# STM32H730_PINOUT.net
KiCad netlist of a schematic drawn in Altium Designer
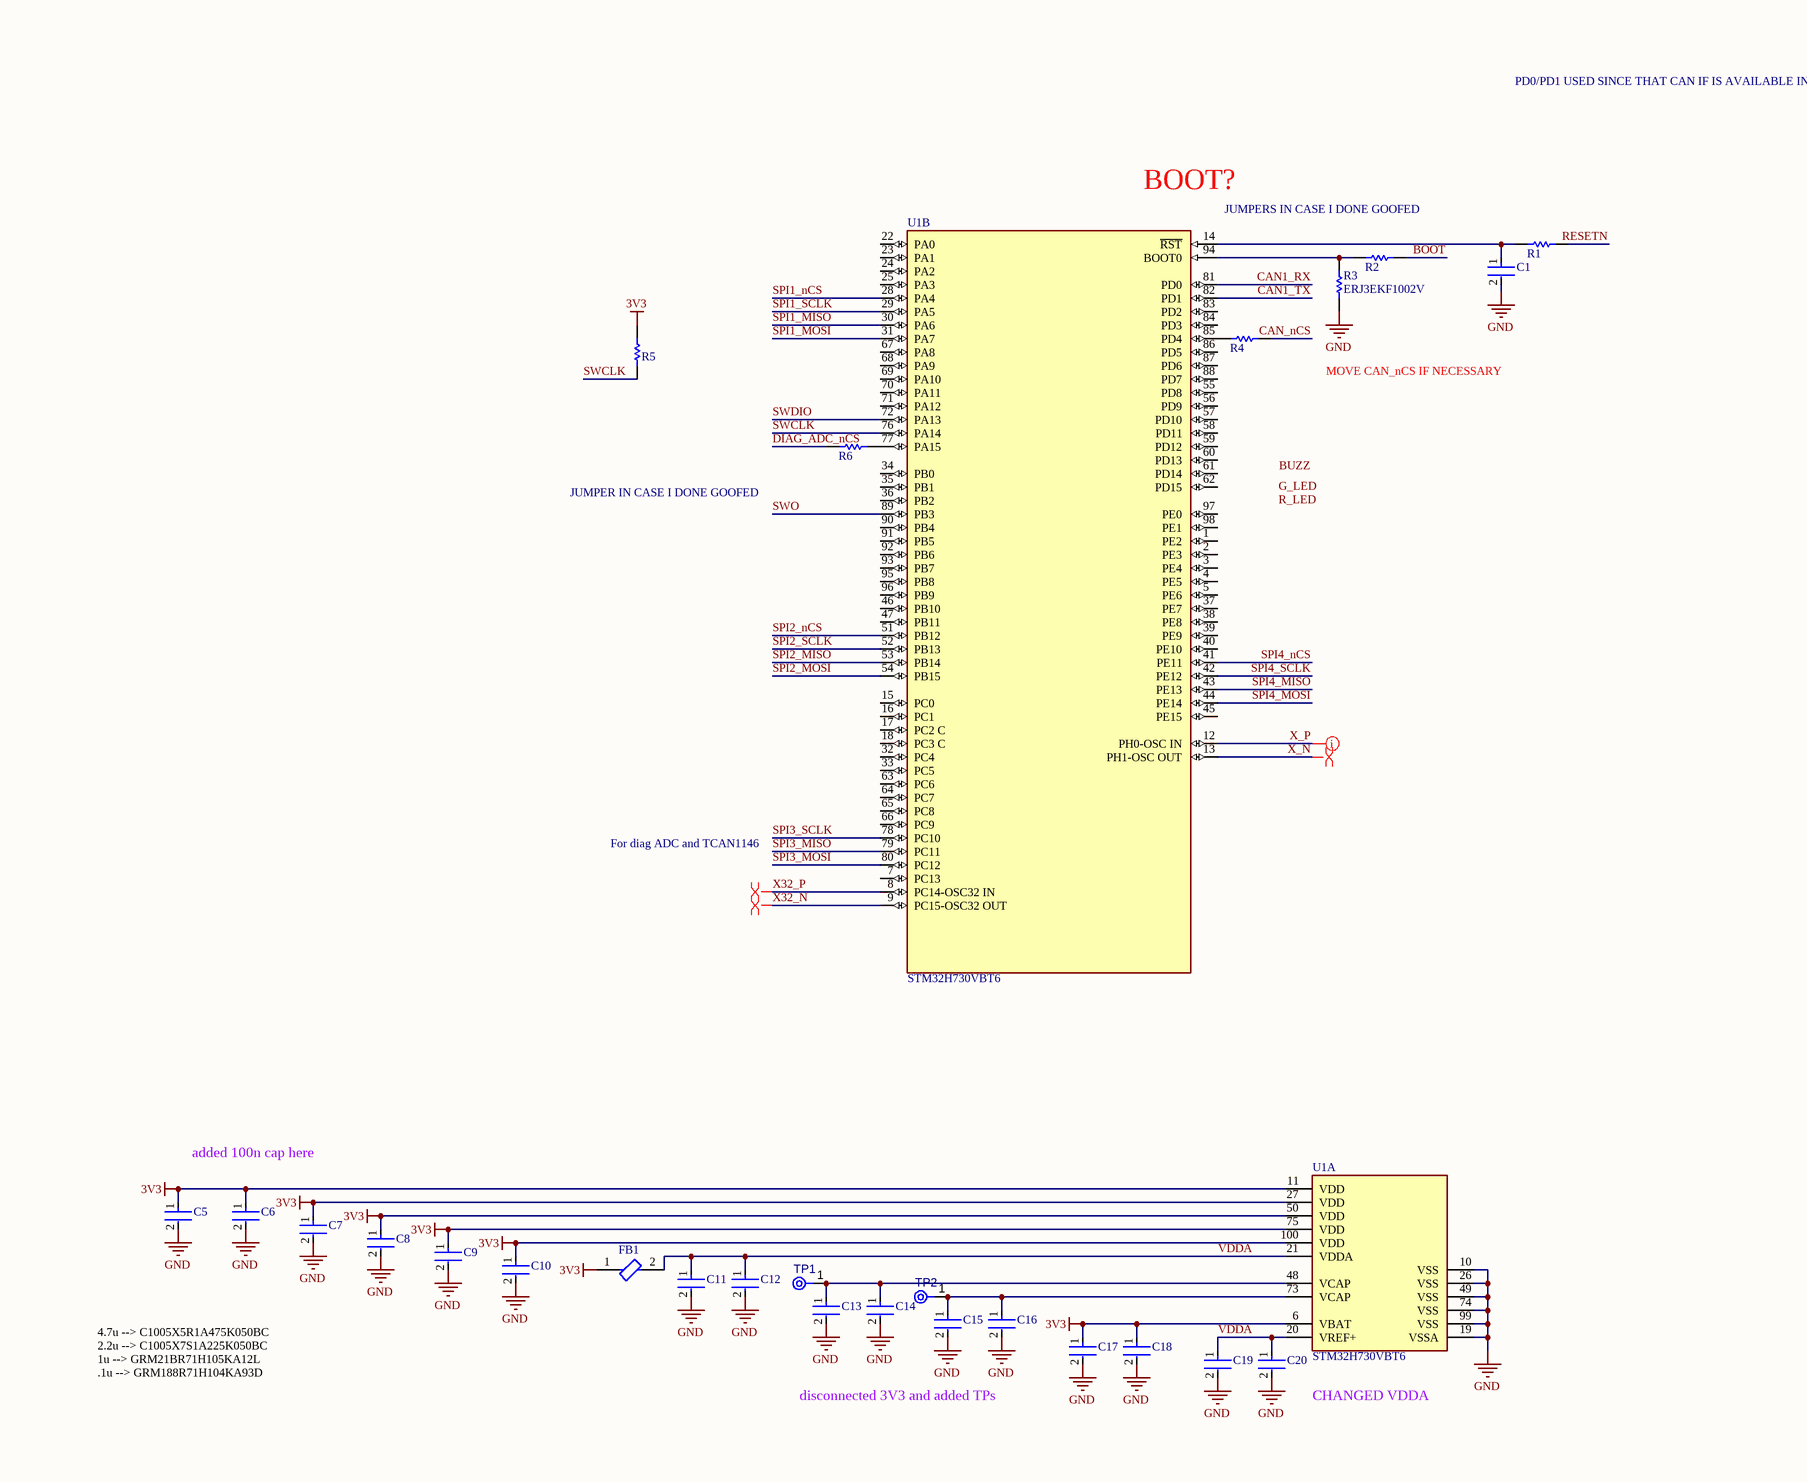
[diagram p0: STM32H730_PINOUT.SchDoc, top left]
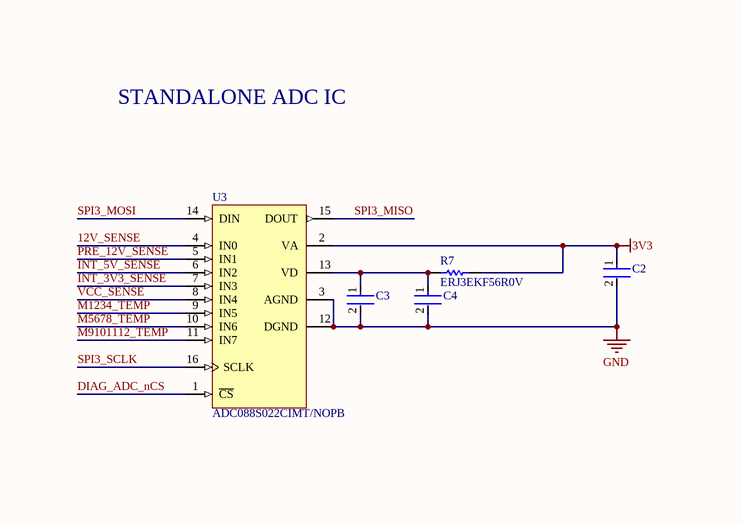
[diagram p1: STM32H730_PINOUT.SchDoc, top middle]
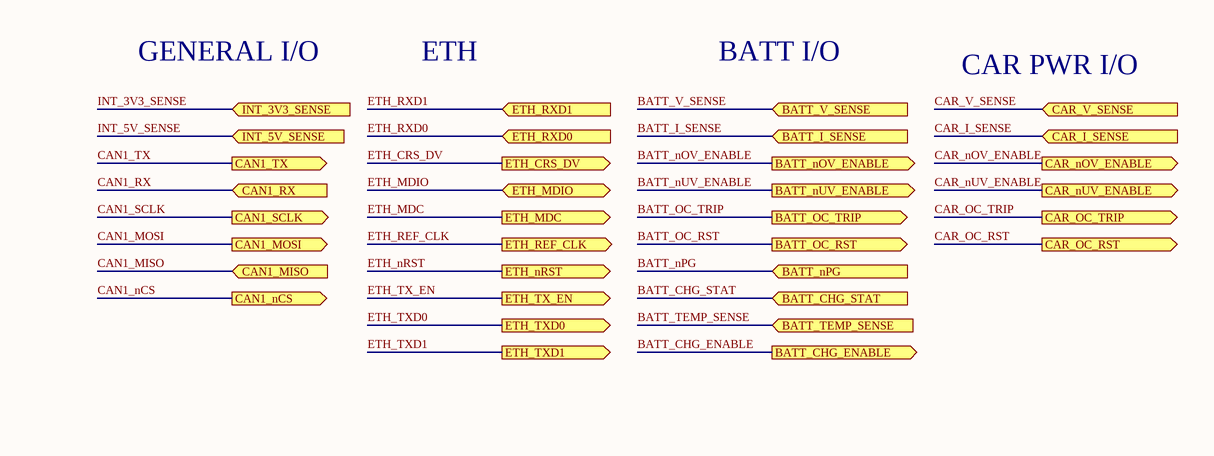
[diagram p2: STM32H730_PINOUT.SchDoc, top right]
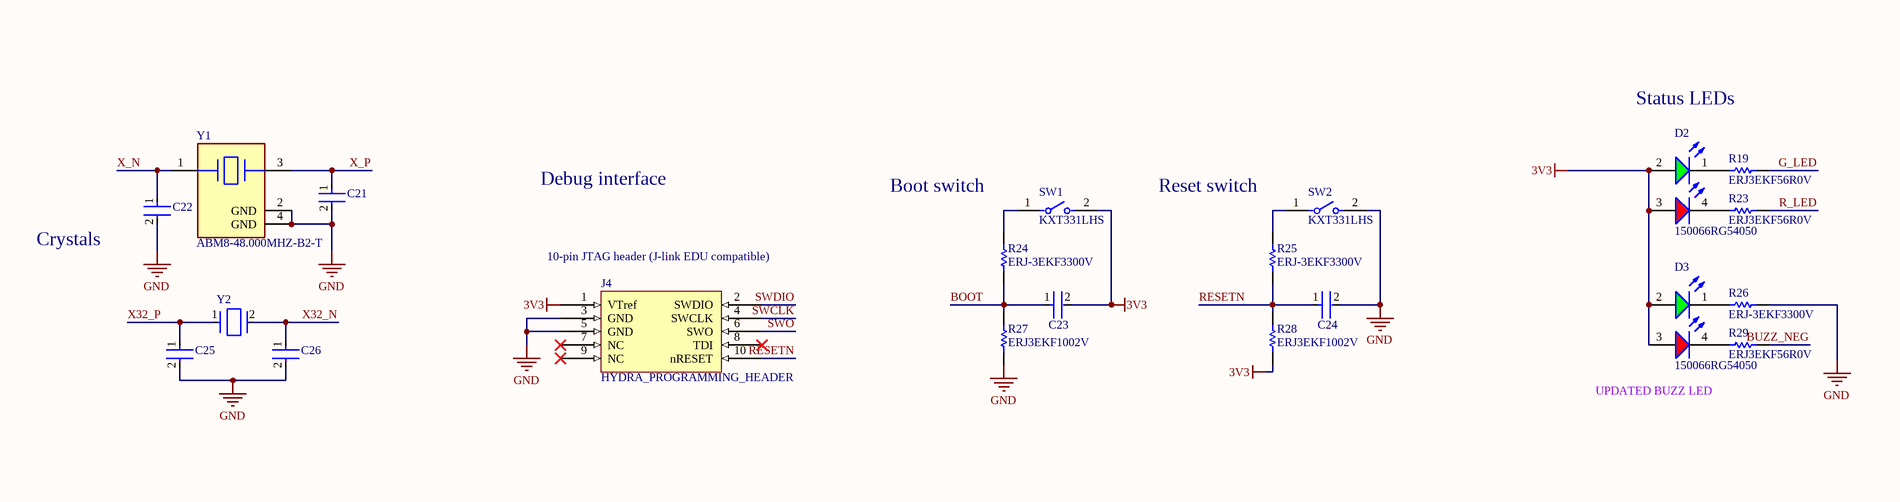
[diagram p3: STM32H730_PINOUT.SchDoc, bottom left]
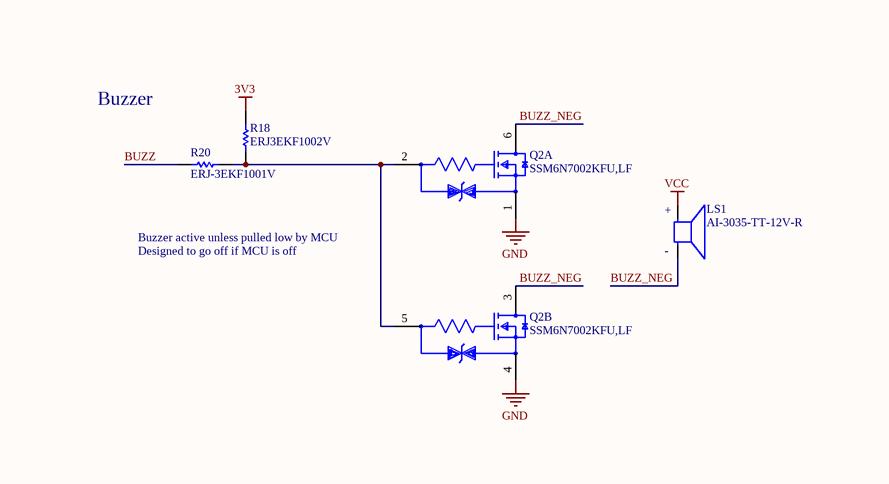
[diagram p4: STM32H730_PINOUT.SchDoc, bottom middle]
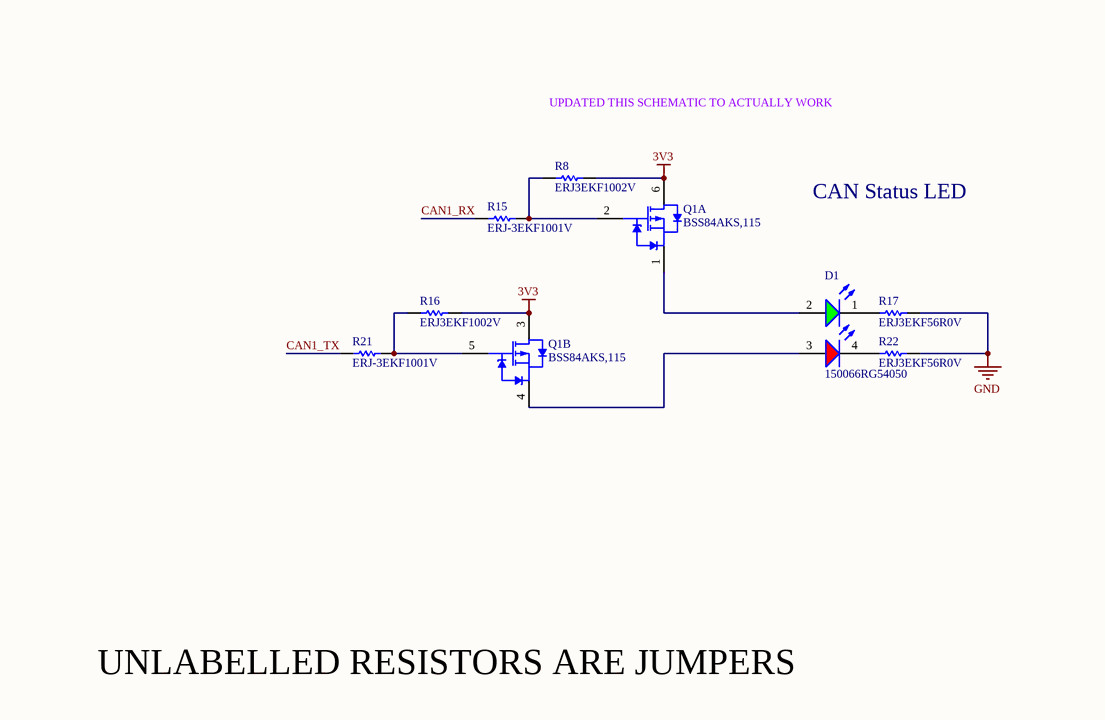
[diagram p5: STM32H730_PINOUT.SchDoc, bottom right]

(export (version "E")
  (design (tool "Eeschema 10.0.6"))
  (components
    (comp (ref "C1")
      (value "GRM188R71H104KA93D")
      (footprint "FP-0402-L_1_0_0_05-W_0_5-IPC_A")
      (description "LARGE PADS, 0402 CAP, CHANGE COMMENT TO MATCH REAL P/N")
      (libsource (lib "Space Concordia") (part "b4654b650e69147ec39a6b967a45e02"))
    )
    (comp (ref "C2")
      (value "GRM188R71H104KA93D")
      (footprint "FP-0402-L_1_0_0_05-W_0_5-IPC_A")
      (description "LARGE PADS, 0402 CAP, CHANGE COMMENT TO MATCH REAL P/N")
      (libsource (lib "Space Concordia") (part "b4654b650e69147ec39a6b967a45e02"))
    )
    (comp (ref "C3")
      (value "GRM188R71H104KA93D")
      (footprint "FP-0402-L_1_0_0_05-W_0_5-IPC_A")
      (description "LARGE PADS, 0402 CAP, CHANGE COMMENT TO MATCH REAL P/N")
      (libsource (lib "Space Concordia") (part "b4654b650e69147ec39a6b967a45e02"))
    )
    (comp (ref "C4")
      (value "GRM188R71H104KA93D")
      (footprint "FP-0402-L_1_0_0_05-W_0_5-IPC_A")
      (description "LARGE PADS, 0402 CAP, CHANGE COMMENT TO MATCH REAL P/N")
      (libsource (lib "Space Concordia") (part "b4654b650e69147ec39a6b967a45e02"))
    )
    (comp (ref "C5")
      (value "C1005X5R1A475K050BC")
      (footprint "FP-0402-L_1_0_0_05-W_0_5-IPC_A")
      (description "LARGE PADS, 0402 CAP, CHANGE COMMENT TO MATCH REAL P/N")
      (libsource (lib "Space Concordia") (part "b4654b650e69147ec39a6b967a45e02"))
    )
    (comp (ref "C6")
      (value "GRM188R71H104KA93D")
      (footprint "FP-0402-L_1_0_0_05-W_0_5-IPC_A")
      (description "LARGE PADS, 0402 CAP, CHANGE COMMENT TO MATCH REAL P/N")
      (libsource (lib "Space Concordia") (part "b4654b650e69147ec39a6b967a45e02"))
    )
    (comp (ref "C7")
      (value "GRM188R71H104KA93D")
      (footprint "FP-0402-L_1_0_0_05-W_0_5-IPC_A")
      (description "LARGE PADS, 0402 CAP, CHANGE COMMENT TO MATCH REAL P/N")
      (libsource (lib "Space Concordia") (part "b4654b650e69147ec39a6b967a45e02"))
    )
    (comp (ref "C8")
      (value "GRM188R71H104KA93D")
      (footprint "FP-0402-L_1_0_0_05-W_0_5-IPC_A")
      (description "LARGE PADS, 0402 CAP, CHANGE COMMENT TO MATCH REAL P/N")
      (libsource (lib "Space Concordia") (part "b4654b650e69147ec39a6b967a45e02"))
    )
    (comp (ref "C9")
      (value "GRM188R71H104KA93D")
      (footprint "FP-0402-L_1_0_0_05-W_0_5-IPC_A")
      (description "LARGE PADS, 0402 CAP, CHANGE COMMENT TO MATCH REAL P/N")
      (libsource (lib "Space Concordia") (part "b4654b650e69147ec39a6b967a45e02"))
    )
    (comp (ref "C10")
      (value "GRM188R71H104KA93D")
      (footprint "FP-0402-L_1_0_0_05-W_0_5-IPC_A")
      (description "LARGE PADS, 0402 CAP, CHANGE COMMENT TO MATCH REAL P/N")
      (libsource (lib "Space Concordia") (part "b4654b650e69147ec39a6b967a45e02"))
    )
    (comp (ref "C11")
      (value "GRM21BR71H105KA12L")
      (footprint "FP-0402-L_1_0_0_05-W_0_5-IPC_A")
      (description "LARGE PADS, 0402 CAP, CHANGE COMMENT TO MATCH REAL P/N")
      (libsource (lib "Space Concordia") (part "b4654b650e69147ec39a6b967a45e02"))
    )
    (comp (ref "C12")
      (value "GRM188R71H104KA93D")
      (footprint "FP-0402-L_1_0_0_05-W_0_5-IPC_A")
      (description "LARGE PADS, 0402 CAP, CHANGE COMMENT TO MATCH REAL P/N")
      (libsource (lib "Space Concordia") (part "b4654b650e69147ec39a6b967a45e02"))
    )
    (comp (ref "C13")
      (value "C1005X7S1A225K050BC")
      (footprint "FP-0402-L_1_0_0_05-W_0_5-IPC_A")
      (description "LARGE PADS, 0402 CAP, CHANGE COMMENT TO MATCH REAL P/N")
      (libsource (lib "Space Concordia") (part "b4654b650e69147ec39a6b967a45e02"))
    )
    (comp (ref "C14")
      (value "GRM188R71H104KA93D")
      (footprint "FP-0402-L_1_0_0_05-W_0_5-IPC_A")
      (description "LARGE PADS, 0402 CAP, CHANGE COMMENT TO MATCH REAL P/N")
      (libsource (lib "Space Concordia") (part "b4654b650e69147ec39a6b967a45e02"))
    )
    (comp (ref "C15")
      (value "C1005X7S1A225K050BC")
      (footprint "FP-0402-L_1_0_0_05-W_0_5-IPC_A")
      (description "LARGE PADS, 0402 CAP, CHANGE COMMENT TO MATCH REAL P/N")
      (libsource (lib "Space Concordia") (part "b4654b650e69147ec39a6b967a45e02"))
    )
    (comp (ref "C16")
      (value "GRM188R71H104KA93D")
      (footprint "FP-0402-L_1_0_0_05-W_0_5-IPC_A")
      (description "LARGE PADS, 0402 CAP, CHANGE COMMENT TO MATCH REAL P/N")
      (libsource (lib "Space Concordia") (part "b4654b650e69147ec39a6b967a45e02"))
    )
    (comp (ref "C17")
      (value "GRM21BR71H105KA12L")
      (footprint "FP-0402-L_1_0_0_05-W_0_5-IPC_A")
      (description "LARGE PADS, 0402 CAP, CHANGE COMMENT TO MATCH REAL P/N")
      (libsource (lib "Space Concordia") (part "b4654b650e69147ec39a6b967a45e02"))
    )
    (comp (ref "C18")
      (value "GRM188R71H104KA93D")
      (footprint "FP-0402-L_1_0_0_05-W_0_5-IPC_A")
      (description "LARGE PADS, 0402 CAP, CHANGE COMMENT TO MATCH REAL P/N")
      (libsource (lib "Space Concordia") (part "b4654b650e69147ec39a6b967a45e02"))
    )
    (comp (ref "C19")
      (value "GRM21BR71H105KA12L")
      (footprint "FP-0402-L_1_0_0_05-W_0_5-IPC_A")
      (description "LARGE PADS, 0402 CAP, CHANGE COMMENT TO MATCH REAL P/N")
      (libsource (lib "Space Concordia") (part "b4654b650e69147ec39a6b967a45e02"))
    )
    (comp (ref "C20")
      (value "GRM188R71H104KA93D")
      (footprint "FP-0402-L_1_0_0_05-W_0_5-IPC_A")
      (description "LARGE PADS, 0402 CAP, CHANGE COMMENT TO MATCH REAL P/N")
      (libsource (lib "Space Concordia") (part "b4654b650e69147ec39a6b967a45e02"))
    )
    (comp (ref "C21")
      (value "DNO")
      (footprint "FP-0402-L_1_0_0_05-W_0_5-IPC_A")
      (description "LARGE PADS, 0402 CAP, CHANGE COMMENT TO MATCH REAL P/N")
      (libsource (lib "Space Concordia") (part "b4654b650e69147ec39a6b967a45e02"))
    )
    (comp (ref "C22")
      (value "DNO")
      (footprint "FP-0402-L_1_0_0_05-W_0_5-IPC_A")
      (description "LARGE PADS, 0402 CAP, CHANGE COMMENT TO MATCH REAL P/N")
      (libsource (lib "Space Concordia") (part "b4654b650e69147ec39a6b967a45e02"))
    )
    (comp (ref "C23")
      (value "GRM188R71H104KA93D")
      (footprint "FP-0402-L_1_0_0_05-W_0_5-IPC_A")
      (description "LARGE PADS, 0402 CAP, CHANGE COMMENT TO MATCH REAL P/N")
      (libsource (lib "Space Concordia") (part "b4654b650e69147ec39a6b967a45e02"))
    )
    (comp (ref "C24")
      (value "GRM188R71H104KA93D")
      (footprint "FP-0402-L_1_0_0_05-W_0_5-IPC_A")
      (description "LARGE PADS, 0402 CAP, CHANGE COMMENT TO MATCH REAL P/N")
      (libsource (lib "Space Concordia") (part "b4654b650e69147ec39a6b967a45e02"))
    )
    (comp (ref "C25")
      (value "04025A180FAT2A")
      (footprint "FP-0402-L_1_0_0_05-W_0_5-IPC_A")
      (description "LARGE PADS, 0402 CAP, CHANGE COMMENT TO MATCH REAL P/N")
      (libsource (lib "Space Concordia") (part "b4654b650e69147ec39a6b967a45e02"))
    )
    (comp (ref "C26")
      (value "04025A180FAT2A")
      (footprint "FP-0402-L_1_0_0_05-W_0_5-IPC_A")
      (description "LARGE PADS, 0402 CAP, CHANGE COMMENT TO MATCH REAL P/N")
      (libsource (lib "Space Concordia") (part "b4654b650e69147ec39a6b967a45e02"))
    )
    (comp (ref "D1")
      (value "150066RG54050")
      (footprint "WL-SBCD_0606")
      (description "Led, Red/Grn, 180Mcd/230Mcd, 624Nm/525Nm Rohs Compliant: Yes")
      (libsource (lib "uORocketry Hardware") (part "WL-SBCD_0606_Red & Green"))
    )
    (comp (ref "D2")
      (value "150066RG54050")
      (footprint "WL-SBCD_0606")
      (description "Led, Red/Grn, 180Mcd/230Mcd, 624Nm/525Nm Rohs Compliant: Yes")
      (libsource (lib "uORocketry Hardware") (part "WL-SBCD_0606_Red & Green"))
    )
    (comp (ref "D3")
      (value "150066RG54050")
      (footprint "WL-SBCD_0606")
      (description "Led, Red/Grn, 180Mcd/230Mcd, 624Nm/525Nm Rohs Compliant: Yes")
      (libsource (lib "uORocketry Hardware") (part "WL-SBCD_0606_Red & Green"))
    )
    (comp (ref "FB1")
      (value "BLM15PX601SN1D")
      (footprint "FP-BLM15-0_05-MFG")
      (description "Chip Ferrite Bead, 0402, 600Ω @ 100MHz, 0.23Ω, 25%, 900mA")
      (fields (field (name "TOLERANCE") "25%"))
      (libsource (lib "Altium Content Vault") (part "5f30dd21d616792df468990f7003faa"))
    )
    (comp (ref "J4")
      (value "HYDRA_PROGRAMMING_HEADER")
      (footprint "3220-10-0300-00-Footprint-1")
      (description "CONN HEADER SMD 10POS 1.27MM (specifically compatible with J-Link EDU cable) PN: 3220-10-0300-00")
      (libsource (lib "uORocketry Hardware") (part "3220-10-0300-00-Symbol-1"))
    )
    (comp (ref "LS1")
      (value "AI-3035-TT-12V-R")
      (footprint "AI-3035-TT-12V-R-Footprint-1")
      (description "Audio Indicator 12V 12mA 110dBA 3.5KHz Resonant Frequency Thru-Hole")
      (libsource (lib "uORocketry Hardware") (part "AI-3035-TT-12V-R"))
    )
    (comp (ref "Q1")
      (value "BSS84AKS,115")
      (footprint "NXP-SOT363_L")
      (description "Dual P-Channel Trench MOSFET, -50 V, -0.16 A, -55 to 150 degC, 6-Pin SOT363, Tape and Reel")
      (fields (field (name "MANUFACTURER") "NXP Semiconductors"))
      (libsource (lib "Altium Content Vault") (part "NXP-PPMOS-SGDSGD-6_A"))
    )
    (comp (ref "Q2")
      (value "SSM6N7002KFU,LF")
      (footprint "FP-SSOP6-P-0_65A-MFG")
      (description "MOSFET 2N-CH 60V 0.3A")
      (libsource (lib "Altium Content Vault") (part "088aa6ac103fdeebe0d1c52ece6b7b9"))
    )
    (comp (ref "R1")
      (value "0402 JUMPER 0 OHM")
      (footprint "RESC1005X40X25NL05T05")
      (description "READ THE NAME")
      (libsource (lib "uORocketry Hardware") (part "RES"))
    )
    (comp (ref "R2")
      (value "0402 JUMPER 0 OHM")
      (footprint "RESC1005X40X25NL05T05")
      (description "READ THE NAME")
      (libsource (lib "uORocketry Hardware") (part "RES"))
    )
    (comp (ref "R3")
      (value "ERJ3EKF1002V")
      (footprint "RESC1609X55X30LL15T15")
      (description "Chip Resistor, 10 KOhm, +/- 1%, 0.1 W, -55 to 155 degC, 0603 (1608 Metric), RoHS, Tape and Reel")
      (fields (field (name "TOLERANCE") "1%") (field (name "MANUFACTURER") "Panasonic"))
      (libsource (lib "Altium Content Vault") (part "RES-2"))
    )
    (comp (ref "R4")
      (value "0402 JUMPER 0 OHM")
      (footprint "RESC1005X40X25NL05T05")
      (description "READ THE NAME")
      (libsource (lib "uORocketry Hardware") (part "RES"))
    )
    (comp (ref "R5")
      (value "ERJ3EKF1002V")
      (footprint "RESC1609X55X30LL15T15")
      (description "Chip Resistor, 10 KOhm, +/- 1%, 0.1 W, -55 to 155 degC, 0603 (1608 Metric), RoHS, Tape and Reel")
      (fields (field (name "TOLERANCE") "1%") (field (name "MANUFACTURER") "Panasonic"))
      (libsource (lib "Altium Content Vault") (part "RES-2"))
    )
    (comp (ref "R6")
      (value "0402 JUMPER 0 OHM")
      (footprint "RESC1005X40X25NL05T05")
      (description "READ THE NAME")
      (libsource (lib "uORocketry Hardware") (part "RES"))
    )
    (comp (ref "R7")
      (value "ERJ3EKF56R0V")
      (footprint "RESC1608X55X30NL15T15")
      (fields (field (name "MANUFACTURER") "Panasonic"))
      (libsource (lib "Altium Content Vault") (part "RES"))
    )
    (comp (ref "R8")
      (value "ERJ3EKF1002V")
      (footprint "RESC1609X55X30LL15T15")
      (description "Chip Resistor, 10 KOhm, +/- 1%, 0.1 W, -55 to 155 degC, 0603 (1608 Metric), RoHS, Tape and Reel")
      (fields (field (name "TOLERANCE") "1%") (field (name "MANUFACTURER") "Panasonic"))
      (libsource (lib "Altium Content Vault") (part "RES-2"))
    )
    (comp (ref "R15")
      (value "ERJ-3EKF1001V")
      (footprint "RESC1608X55X30LL15T15")
      (fields (field (name "MANUFACTURER") "Panasonic"))
      (libsource (lib "Altium Content Vault") (part "RES"))
    )
    (comp (ref "R16")
      (value "ERJ3EKF1002V")
      (footprint "RESC1609X55X30LL15T15")
      (description "Chip Resistor, 10 KOhm, +/- 1%, 0.1 W, -55 to 155 degC, 0603 (1608 Metric), RoHS, Tape and Reel")
      (fields (field (name "TOLERANCE") "1%") (field (name "MANUFACTURER") "Panasonic"))
      (libsource (lib "Altium Content Vault") (part "RES-2"))
    )
    (comp (ref "R17")
      (value "ERJ3EKF56R0V")
      (footprint "RESC1608X55X30NL15T15")
      (fields (field (name "MANUFACTURER") "Panasonic"))
      (libsource (lib "Altium Content Vault") (part "RES"))
    )
    (comp (ref "R18")
      (value "ERJ3EKF1002V")
      (footprint "RESC1609X55X30LL15T15")
      (description "Chip Resistor, 10 KOhm, +/- 1%, 0.1 W, -55 to 155 degC, 0603 (1608 Metric), RoHS, Tape and Reel")
      (fields (field (name "TOLERANCE") "1%") (field (name "MANUFACTURER") "Panasonic"))
      (libsource (lib "Altium Content Vault") (part "RES-2"))
    )
    (comp (ref "R19")
      (value "ERJ3EKF56R0V")
      (footprint "RESC1608X55X30NL15T15")
      (fields (field (name "MANUFACTURER") "Panasonic"))
      (libsource (lib "Altium Content Vault") (part "RES"))
    )
    (comp (ref "R20")
      (value "ERJ-3EKF1001V")
      (footprint "RESC1608X55X30LL15T15")
      (fields (field (name "MANUFACTURER") "Panasonic"))
      (libsource (lib "Altium Content Vault") (part "RES"))
    )
    (comp (ref "R21")
      (value "ERJ-3EKF1001V")
      (footprint "RESC1608X55X30LL15T15")
      (fields (field (name "MANUFACTURER") "Panasonic"))
      (libsource (lib "Altium Content Vault") (part "RES"))
    )
    (comp (ref "R22")
      (value "ERJ3EKF56R0V")
      (footprint "RESC1608X55X30NL15T15")
      (fields (field (name "MANUFACTURER") "Panasonic"))
      (libsource (lib "Altium Content Vault") (part "RES"))
    )
    (comp (ref "R23")
      (value "ERJ3EKF56R0V")
      (footprint "RESC1608X55X30NL15T15")
      (fields (field (name "MANUFACTURER") "Panasonic"))
      (libsource (lib "Altium Content Vault") (part "RES"))
    )
    (comp (ref "R24")
      (value "ERJ-3EKF3300V")
      (footprint "RESC1608X55X30LL15T15")
      (description "Chip Resistor, 330 Ohm, +/- 1%, 0.1 W, -55 to 155 degC, 0603 (1608 Metric), RoHS, Tape and Reel")
      (libsource (lib "Altium Content Vault") (part "RES-2"))
    )
    (comp (ref "R25")
      (value "ERJ-3EKF3300V")
      (footprint "RESC1608X55X30LL15T15")
      (description "Chip Resistor, 330 Ohm, +/- 1%, 0.1 W, -55 to 155 degC, 0603 (1608 Metric), RoHS, Tape and Reel")
      (libsource (lib "Altium Content Vault") (part "RES-2"))
    )
    (comp (ref "R26")
      (value "ERJ-3EKF3300V")
      (footprint "RESC1608X55X30LL15T15")
      (description "Chip Resistor, 330 Ohm, +/- 1%, 0.1 W, -55 to 155 degC, 0603 (1608 Metric), RoHS, Tape and Reel")
      (libsource (lib "Altium Content Vault") (part "RES-2"))
    )
    (comp (ref "R27")
      (value "ERJ3EKF1002V")
      (footprint "RESC1609X55X30LL15T15")
      (description "Chip Resistor, 10 KOhm, +/- 1%, 0.1 W, -55 to 155 degC, 0603 (1608 Metric), RoHS, Tape and Reel")
      (fields (field (name "TOLERANCE") "1%") (field (name "MANUFACTURER") "Panasonic"))
      (libsource (lib "Altium Content Vault") (part "RES-2"))
    )
    (comp (ref "R28")
      (value "ERJ3EKF1002V")
      (footprint "RESC1609X55X30LL15T15")
      (description "Chip Resistor, 10 KOhm, +/- 1%, 0.1 W, -55 to 155 degC, 0603 (1608 Metric), RoHS, Tape and Reel")
      (fields (field (name "TOLERANCE") "1%") (field (name "MANUFACTURER") "Panasonic"))
      (libsource (lib "Altium Content Vault") (part "RES-2"))
    )
    (comp (ref "R29")
      (value "ERJ3EKF56R0V")
      (footprint "RESC1608X55X30NL15T15")
      (fields (field (name "MANUFACTURER") "Panasonic"))
      (libsource (lib "Altium Content Vault") (part "RES"))
    )
    (comp (ref "SW1")
      (value "KXT331LHS")
      (footprint "FP-KXT331LHS-MFG")
      (description "SWITCH TACTILE SPST-NO 0.02A 15V")
      (libsource (lib "Altium Content Vault") (part "bb27bde45df87f1f469753f287ef5ae"))
    )
    (comp (ref "SW2")
      (value "KXT331LHS")
      (footprint "FP-KXT331LHS-MFG")
      (description "SWITCH TACTILE SPST-NO 0.02A 15V")
      (libsource (lib "Altium Content Vault") (part "bb27bde45df87f1f469753f287ef5ae"))
    )
    (comp (ref "TP1")
      (value "TPAD6R")
      (footprint "TP06R")
      (description "0.6mm round")
      (libsource (lib "uORocketry Hardware") (part "CMP-001-0001-4"))
    )
    (comp (ref "TP2")
      (value "TPAD6R")
      (footprint "TP06R")
      (description "0.6mm round")
      (libsource (lib "uORocketry Hardware") (part "CMP-001-0001-4"))
    )
    (comp (ref "U1")
      (value "STM32H730VBT6")
      (footprint "FP-LQFP100-1L-IPC_C")
      (description "IC MCU 32BIT 128KB FLASH 100LQFP")
      (libsource (lib "Altium Content Vault") (part "44dc6501260a4d92b846760feb66c20"))
    )
    (comp (ref "U3")
      (value "ADC088S022CIMT/NOPB")
      (footprint "MTC16_L")
      (description "8-Channel, 50 kSPS to 200 kSPS, 8-Bit A/D Converter, 16-pin TSSOP, Pb-Free")
      (fields (field (name "MANUFACTURER") "National Semiconductor"))
      (libsource (lib "Altium Content Vault") (part "CON-ADC-ADC108S052CIMT"))
    )
    (comp (ref "Y1")
      (value "ABM8-48.000MHZ-B2-T")
      (footprint "FP-ABM8-MFG")
      (description "Crystal 48MHz ±20ppm 18pF SMD-4 3.2mm x 2.5mm")
      (fields (field (name "TOLERANCE") "20ppm"))
      (libsource (lib "Altium Content Vault") (part "dfdb7f9a12507849fb681da9a70121c"))
    )
    (comp (ref "Y2")
      (value "ECS-.327-12.5-1210-TR")
      (footprint "FP-ECX-1210-MFG")
      (description "CRYSTAL 32.7680KHZ 12.5PF SMD")
      (fields
        (field (name "OCTOPART") "https://octopart.com/ecs-.327-12.5-1210-tr-ecs+international-81221340")
        (field (name "TOLERANCE") "20ppm")
      )
      (libsource (lib "Altium Content Vault") (part "99724985039315a44fd0d1401b84e49"))
    )
  )
  (nets
    (net (code "1") (name "/12V_SENSE") (class "Default")
      (node (ref "U3") (pin "4") (pinfunction "IN0_4") (pintype "input"))
    )
    (net (code "12") (name "/BOOT") (class "Default")
      (node (ref "C23") (pin "1") (pinfunction "1_1") (pintype "passive"))
      (node (ref "R2") (pin "2") (pinfunction "2_2") (pintype "passive"))
      (node (ref "R24") (pin "1") (pinfunction "1_1") (pintype "passive"))
      (node (ref "R27") (pin "2") (pinfunction "2_2") (pintype "passive"))
    )
    (net (code "13") (name "/BUZZ") (class "Default")
      (node (ref "R20") (pin "1") (pinfunction "1_1") (pintype "passive"))
    )
    (net (code "14") (name "/BUZZ_NEG") (class "Default")
      (node (ref "LS1") (pin "N") (pinfunction "N_N") (pintype "passive"))
      (node (ref "Q2") (pin "3") (pinfunction "Drain2_3") (pintype "passive"))
      (node (ref "Q2") (pin "6") (pinfunction "Drain1_6") (pintype "passive"))
      (node (ref "R29") (pin "1") (pinfunction "1_1") (pintype "passive"))
    )
    (net (code "17") (name "/CAN1_RX") (class "Default")
      (node (ref "R15") (pin "1") (pinfunction "1_1") (pintype "passive"))
      (node (ref "U1") (pin "81") (pinfunction "PD0_81") (pintype "bidirectional"))
    )
    (net (code "19") (name "/CAN1_TX") (class "Default")
      (node (ref "R21") (pin "1") (pinfunction "1_1") (pintype "passive"))
      (node (ref "U1") (pin "82") (pinfunction "PD1_82") (pintype "bidirectional"))
    )
    (net (code "21") (name "/CAN_nCS") (class "Default")
      (node (ref "R4") (pin "2") (pinfunction "2_2") (pintype "passive"))
    )
    (net (code "28") (name "/DIAG_ADC_nCS") (class "Default")
      (node (ref "R6") (pin "1") (pinfunction "1_1") (pintype "passive"))
      (node (ref "U3") (pin "1") (pinfunction "~{CS}_1") (pintype "input"))
    )
    (net (code "39") (name "/G_LED") (class "Default")
      (node (ref "R19") (pin "1") (pinfunction "1_1") (pintype "passive"))
    )
    (net (code "40") (name "/INT_3V3_SENSE") (class "Default")
      (node (ref "U3") (pin "7") (pinfunction "IN3_7") (pintype "input"))
    )
    (net (code "41") (name "/INT_5V_SENSE") (class "Default")
      (node (ref "U3") (pin "6") (pinfunction "IN2_6") (pintype "input"))
    )
    (net (code "42") (name "/M1234_TEMP") (class "Default")
      (node (ref "U3") (pin "9") (pinfunction "IN5_9") (pintype "input"))
    )
    (net (code "43") (name "/M5678_TEMP") (class "Default")
      (node (ref "U3") (pin "10") (pinfunction "IN6_10") (pintype "input"))
    )
    (net (code "44") (name "/M9101112_TEMP") (class "Default")
      (node (ref "U3") (pin "11") (pinfunction "IN7_11") (pintype "input"))
    )
    (net (code "45") (name "/PRE_12V_SENSE") (class "Default")
      (node (ref "U3") (pin "5") (pinfunction "IN1_5") (pintype "input"))
    )
    (net (code "46") (name "/RESETN") (class "Default")
      (node (ref "C24") (pin "1") (pinfunction "1_1") (pintype "passive"))
      (node (ref "J4") (pin "10") (pinfunction "nRESET_10") (pintype "input"))
      (node (ref "R1") (pin "2") (pinfunction "2_2") (pintype "passive"))
      (node (ref "R25") (pin "1") (pinfunction "1_1") (pintype "passive"))
      (node (ref "R28") (pin "2") (pinfunction "2_2") (pintype "passive"))
    )
    (net (code "47") (name "/R_LED") (class "Default")
      (node (ref "R23") (pin "1") (pinfunction "1_1") (pintype "passive"))
    )
    (net (code "48") (name "/SPI1_MISO") (class "Default")
      (node (ref "U1") (pin "30") (pinfunction "PA6_30") (pintype "bidirectional"))
    )
    (net (code "49") (name "/SPI1_MOSI") (class "Default")
      (node (ref "U1") (pin "31") (pinfunction "PA7_31") (pintype "bidirectional"))
    )
    (net (code "50") (name "/SPI1_SCLK") (class "Default")
      (node (ref "U1") (pin "29") (pinfunction "PA5_29") (pintype "bidirectional"))
    )
    (net (code "51") (name "/SPI1_nCS") (class "Default")
      (node (ref "U1") (pin "28") (pinfunction "PA4_28") (pintype "bidirectional"))
    )
    (net (code "52") (name "/SPI2_MISO") (class "Default")
      (node (ref "U1") (pin "53") (pinfunction "PB14_53") (pintype "bidirectional"))
    )
    (net (code "53") (name "/SPI2_MOSI") (class "Default")
      (node (ref "U1") (pin "54") (pinfunction "PB15_54") (pintype "bidirectional"))
    )
    (net (code "54") (name "/SPI2_SCLK") (class "Default")
      (node (ref "U1") (pin "52") (pinfunction "PB13_52") (pintype "bidirectional"))
    )
    (net (code "55") (name "/SPI2_nCS") (class "Default")
      (node (ref "U1") (pin "51") (pinfunction "PB12_51") (pintype "bidirectional"))
    )
    (net (code "56") (name "/SPI3_MISO") (class "Default")
      (node (ref "U1") (pin "79") (pinfunction "PC11_79") (pintype "bidirectional"))
      (node (ref "U3") (pin "15") (pinfunction "DOUT_15") (pintype "output"))
    )
    (net (code "57") (name "/SPI3_MOSI") (class "Default")
      (node (ref "U1") (pin "80") (pinfunction "PC12_80") (pintype "bidirectional"))
      (node (ref "U3") (pin "14") (pinfunction "DIN_14") (pintype "input"))
    )
    (net (code "58") (name "/SPI3_SCLK") (class "Default")
      (node (ref "U1") (pin "78") (pinfunction "PC10_78") (pintype "bidirectional"))
      (node (ref "U3") (pin "16") (pinfunction "SCLK_16") (pintype "input"))
    )
    (net (code "59") (name "/SPI4_MISO") (class "Default")
      (node (ref "U1") (pin "43") (pinfunction "PE13_43") (pintype "bidirectional"))
    )
    (net (code "60") (name "/SPI4_MOSI") (class "Default")
      (node (ref "U1") (pin "44") (pinfunction "PE14_44") (pintype "bidirectional"))
    )
    (net (code "61") (name "/SPI4_SCLK") (class "Default")
      (node (ref "U1") (pin "42") (pinfunction "PE12_42") (pintype "bidirectional"))
    )
    (net (code "62") (name "/SPI4_nCS") (class "Default")
      (node (ref "U1") (pin "41") (pinfunction "PE11_41") (pintype "bidirectional"))
    )
    (net (code "63") (name "/SWCLK") (class "Default")
      (node (ref "J4") (pin "4") (pinfunction "SWCLK_4") (pintype "input"))
      (node (ref "R5") (pin "2") (pinfunction "2_2") (pintype "passive"))
      (node (ref "U1") (pin "76") (pinfunction "PA14_76") (pintype "bidirectional"))
    )
    (net (code "64") (name "/SWDIO") (class "Default")
      (node (ref "J4") (pin "2") (pinfunction "SWDIO_2") (pintype "input"))
      (node (ref "U1") (pin "72") (pinfunction "PA13_72") (pintype "bidirectional"))
    )
    (net (code "65") (name "/SWO") (class "Default")
      (node (ref "J4") (pin "6") (pinfunction "SWO_6") (pintype "input"))
      (node (ref "U1") (pin "89") (pinfunction "PB3_89") (pintype "bidirectional"))
    )
    (net (code "66") (name "/VCC_SENSE") (class "Default")
      (node (ref "U3") (pin "8") (pinfunction "IN4_8") (pintype "input"))
    )
    (net (code "67") (name "/VDDA") (class "Default")
      (node (ref "C11") (pin "1") (pinfunction "1_1") (pintype "passive"))
      (node (ref "C12") (pin "1") (pinfunction "1_1") (pintype "passive"))
      (node (ref "C19") (pin "1") (pinfunction "1_1") (pintype "passive"))
      (node (ref "C20") (pin "1") (pinfunction "1_1") (pintype "passive"))
      (node (ref "FB1") (pin "2") (pinfunction "2_2") (pintype "passive"))
      (node (ref "U1") (pin "20") (pinfunction "VREF+_20") (pintype "power_in"))
      (node (ref "U1") (pin "21") (pinfunction "VDDA_21") (pintype "power_in"))
    )
    (net (code "68") (name "/X32_N") (class "Default")
      (node (ref "C26") (pin "1") (pinfunction "1_1") (pintype "passive"))
      (node (ref "U1") (pin "9") (pinfunction "PC15-OSC32_OUT_9") (pintype "bidirectional"))
      (node (ref "Y2") (pin "2") (pinfunction "Out/In_2") (pintype "passive"))
    )
    (net (code "69") (name "/X32_P") (class "Default")
      (node (ref "C25") (pin "1") (pinfunction "1_1") (pintype "passive"))
      (node (ref "U1") (pin "8") (pinfunction "PC14-OSC32_IN_8") (pintype "bidirectional"))
      (node (ref "Y2") (pin "1") (pinfunction "In/Out_1") (pintype "passive"))
    )
    (net (code "70") (name "/X_N") (class "Default")
      (node (ref "C22") (pin "1") (pinfunction "1_1") (pintype "passive"))
      (node (ref "U1") (pin "13") (pinfunction "PH1-OSC_OUT_13") (pintype "bidirectional"))
      (node (ref "Y1") (pin "1") (pinfunction "1_1") (pintype "passive"))
    )
    (net (code "71") (name "/X_P") (class "Default")
      (node (ref "C21") (pin "1") (pinfunction "1_1") (pintype "passive"))
      (node (ref "U1") (pin "12") (pinfunction "PH0-OSC_IN_12") (pintype "bidirectional"))
      (node (ref "Y1") (pin "3") (pinfunction "3_3") (pintype "passive"))
    )
    (net (code "72") (name "3V3") (class "Default")
      (node (ref "C10") (pin "1") (pinfunction "1_1") (pintype "passive"))
      (node (ref "C17") (pin "1") (pinfunction "1_1") (pintype "passive"))
      (node (ref "C18") (pin "1") (pinfunction "1_1") (pintype "passive"))
      (node (ref "C2") (pin "1") (pinfunction "1_1") (pintype "passive"))
      (node (ref "C23") (pin "2") (pinfunction "2_2") (pintype "passive"))
      (node (ref "C5") (pin "1") (pinfunction "1_1") (pintype "passive"))
      (node (ref "C6") (pin "1") (pinfunction "1_1") (pintype "passive"))
      (node (ref "C7") (pin "1") (pinfunction "1_1") (pintype "passive"))
      (node (ref "C8") (pin "1") (pinfunction "1_1") (pintype "passive"))
      (node (ref "C9") (pin "1") (pinfunction "1_1") (pintype "passive"))
      (node (ref "D2") (pin "2") (pinfunction "A_2") (pintype "passive"))
      (node (ref "D2") (pin "3") (pinfunction "A_3") (pintype "passive"))
      (node (ref "D3") (pin "2") (pinfunction "A_2") (pintype "passive"))
      (node (ref "D3") (pin "3") (pinfunction "A_3") (pintype "passive"))
      (node (ref "FB1") (pin "1") (pinfunction "1_1") (pintype "passive"))
      (node (ref "J4") (pin "1") (pinfunction "VTref_1") (pintype "input"))
      (node (ref "Q1") (pin "3") (pinfunction "D2_3") (pintype "passive"))
      (node (ref "Q1") (pin "6") (pinfunction "D1_6") (pintype "passive"))
      (node (ref "R16") (pin "2") (pinfunction "2_2") (pintype "passive"))
      (node (ref "R18") (pin "2") (pinfunction "2_2") (pintype "passive"))
      (node (ref "R28") (pin "1") (pinfunction "1_1") (pintype "passive"))
      (node (ref "R5") (pin "1") (pinfunction "1_1") (pintype "passive"))
      (node (ref "R7") (pin "1") (pinfunction "1_1") (pintype "passive"))
      (node (ref "R8") (pin "2") (pinfunction "2_2") (pintype "passive"))
      (node (ref "SW1") (pin "2") (pinfunction "2_2") (pintype "passive"))
      (node (ref "U1") (pin "100") (pinfunction "VDD_100") (pintype "power_in"))
      (node (ref "U1") (pin "11") (pinfunction "VDD_11") (pintype "power_in"))
      (node (ref "U1") (pin "27") (pinfunction "VDD_27") (pintype "power_in"))
      (node (ref "U1") (pin "50") (pinfunction "VDD_50") (pintype "power_in"))
      (node (ref "U1") (pin "6") (pinfunction "VBAT_6") (pintype "power_in"))
      (node (ref "U1") (pin "75") (pinfunction "VDD_75") (pintype "power_in"))
      (node (ref "U3") (pin "2") (pinfunction "VA_2") (pintype "power_in"))
    )
    (net (code "73") (name "GND") (class "Default")
      (node (ref "C1") (pin "2") (pinfunction "2_2") (pintype "passive"))
      (node (ref "C10") (pin "2") (pinfunction "2_2") (pintype "passive"))
      (node (ref "C11") (pin "2") (pinfunction "2_2") (pintype "passive"))
      (node (ref "C12") (pin "2") (pinfunction "2_2") (pintype "passive"))
      (node (ref "C13") (pin "2") (pinfunction "2_2") (pintype "passive"))
      (node (ref "C14") (pin "2") (pinfunction "2_2") (pintype "passive"))
      (node (ref "C15") (pin "2") (pinfunction "2_2") (pintype "passive"))
      (node (ref "C16") (pin "2") (pinfunction "2_2") (pintype "passive"))
      (node (ref "C17") (pin "2") (pinfunction "2_2") (pintype "passive"))
      (node (ref "C18") (pin "2") (pinfunction "2_2") (pintype "passive"))
      (node (ref "C19") (pin "2") (pinfunction "2_2") (pintype "passive"))
      (node (ref "C2") (pin "2") (pinfunction "2_2") (pintype "passive"))
      (node (ref "C20") (pin "2") (pinfunction "2_2") (pintype "passive"))
      (node (ref "C21") (pin "2") (pinfunction "2_2") (pintype "passive"))
      (node (ref "C22") (pin "2") (pinfunction "2_2") (pintype "passive"))
      (node (ref "C24") (pin "2") (pinfunction "2_2") (pintype "passive"))
      (node (ref "C25") (pin "2") (pinfunction "2_2") (pintype "passive"))
      (node (ref "C26") (pin "2") (pinfunction "2_2") (pintype "passive"))
      (node (ref "C3") (pin "2") (pinfunction "2_2") (pintype "passive"))
      (node (ref "C4") (pin "2") (pinfunction "2_2") (pintype "passive"))
      (node (ref "C5") (pin "2") (pinfunction "2_2") (pintype "passive"))
      (node (ref "C6") (pin "2") (pinfunction "2_2") (pintype "passive"))
      (node (ref "C7") (pin "2") (pinfunction "2_2") (pintype "passive"))
      (node (ref "C8") (pin "2") (pinfunction "2_2") (pintype "passive"))
      (node (ref "C9") (pin "2") (pinfunction "2_2") (pintype "passive"))
      (node (ref "J4") (pin "3") (pinfunction "GND_3") (pintype "input"))
      (node (ref "J4") (pin "5") (pinfunction "GND_5") (pintype "input"))
      (node (ref "Q2") (pin "1") (pinfunction "Source1_1") (pintype "passive"))
      (node (ref "Q2") (pin "4") (pinfunction "Source2_4") (pintype "passive"))
      (node (ref "R17") (pin "1") (pinfunction "1_1") (pintype "passive"))
      (node (ref "R22") (pin "1") (pinfunction "1_1") (pintype "passive"))
      (node (ref "R26") (pin "2") (pinfunction "2_2") (pintype "passive"))
      (node (ref "R27") (pin "1") (pinfunction "1_1") (pintype "passive"))
      (node (ref "R3") (pin "1") (pinfunction "1_1") (pintype "passive"))
      (node (ref "SW2") (pin "2") (pinfunction "2_2") (pintype "passive"))
      (node (ref "U1") (pin "10") (pinfunction "VSS_10") (pintype "power_in"))
      (node (ref "U1") (pin "19") (pinfunction "VSSA_19") (pintype "power_in"))
      (node (ref "U1") (pin "26") (pinfunction "VSS_26") (pintype "power_in"))
      (node (ref "U1") (pin "49") (pinfunction "VSS_49") (pintype "power_in"))
      (node (ref "U1") (pin "74") (pinfunction "VSS_74") (pintype "power_in"))
      (node (ref "U1") (pin "99") (pinfunction "VSS_99") (pintype "power_in"))
      (node (ref "U3") (pin "12") (pinfunction "DGND_12") (pintype "power_in"))
      (node (ref "U3") (pin "3") (pinfunction "AGND_3") (pintype "power_in"))
      (node (ref "Y1") (pin "2") (pinfunction "GND_2") (pintype "power_in"))
      (node (ref "Y1") (pin "4") (pinfunction "GND_4") (pintype "power_in"))
    )
    (net (code "74") (name "Net-(D1-K-Pad1)") (class "Default")
      (node (ref "D1") (pin "1") (pinfunction "K_1") (pintype "passive"))
      (node (ref "R17") (pin "2") (pinfunction "2_2") (pintype "passive"))
    )
    (net (code "75") (name "Net-(D1-K-Pad4)") (class "Default")
      (node (ref "D1") (pin "4") (pinfunction "K_4") (pintype "passive"))
      (node (ref "R22") (pin "2") (pinfunction "2_2") (pintype "passive"))
    )
    (net (code "76") (name "Net-(D2-K-Pad1)") (class "Default")
      (node (ref "D2") (pin "1") (pinfunction "K_1") (pintype "passive"))
      (node (ref "R19") (pin "2") (pinfunction "2_2") (pintype "passive"))
    )
    (net (code "77") (name "Net-(D2-K-Pad4)") (class "Default")
      (node (ref "D2") (pin "4") (pinfunction "K_4") (pintype "passive"))
      (node (ref "R23") (pin "2") (pinfunction "2_2") (pintype "passive"))
    )
    (net (code "78") (name "Net-(D3-K-Pad1)") (class "Default")
      (node (ref "D3") (pin "1") (pinfunction "K_1") (pintype "passive"))
      (node (ref "R26") (pin "1") (pinfunction "1_1") (pintype "passive"))
    )
    (net (code "79") (name "Net-(D3-K-Pad4)") (class "Default")
      (node (ref "D3") (pin "4") (pinfunction "K_4") (pintype "passive"))
      (node (ref "R29") (pin "2") (pinfunction "2_2") (pintype "passive"))
    )
    (net (code "80") (name "Net-(Q1A-G1)") (class "Default")
      (node (ref "Q1") (pin "2") (pinfunction "G1_2") (pintype "passive"))
      (node (ref "R15") (pin "2") (pinfunction "2_2") (pintype "passive"))
      (node (ref "R8") (pin "1") (pinfunction "1_1") (pintype "passive"))
    )
    (net (code "81") (name "Net-(Q1A-S1)") (class "Default")
      (node (ref "D1") (pin "2") (pinfunction "A_2") (pintype "passive"))
      (node (ref "Q1") (pin "1") (pinfunction "S1_1") (pintype "passive"))
    )
    (net (code "82") (name "Net-(Q1B-G2)") (class "Default")
      (node (ref "Q1") (pin "5") (pinfunction "G2_5") (pintype "passive"))
      (node (ref "R16") (pin "1") (pinfunction "1_1") (pintype "passive"))
      (node (ref "R21") (pin "2") (pinfunction "2_2") (pintype "passive"))
    )
    (net (code "83") (name "Net-(Q1B-S2)") (class "Default")
      (node (ref "D1") (pin "3") (pinfunction "A_3") (pintype "passive"))
      (node (ref "Q1") (pin "4") (pinfunction "S2_4") (pintype "passive"))
    )
    (net (code "84") (name "Net-(Q2A-Gate1)") (class "Default")
      (node (ref "Q2") (pin "2") (pinfunction "Gate1_2") (pintype "passive"))
      (node (ref "Q2") (pin "5") (pinfunction "Gate2_5") (pintype "passive"))
      (node (ref "R18") (pin "1") (pinfunction "1_1") (pintype "passive"))
      (node (ref "R20") (pin "2") (pinfunction "2_2") (pintype "passive"))
    )
    (net (code "85") (name "Net-(R24-Pad2)") (class "Default")
      (node (ref "R24") (pin "2") (pinfunction "2_2") (pintype "passive"))
      (node (ref "SW1") (pin "1") (pinfunction "1_1") (pintype "passive"))
    )
    (net (code "86") (name "Net-(R25-Pad2)") (class "Default")
      (node (ref "R25") (pin "2") (pinfunction "2_2") (pintype "passive"))
      (node (ref "SW2") (pin "1") (pinfunction "1_1") (pintype "passive"))
    )
    (net (code "87") (name "Net-(TP1-TP)") (class "Default")
      (node (ref "C13") (pin "1") (pinfunction "1_1") (pintype "passive"))
      (node (ref "C14") (pin "1") (pinfunction "1_1") (pintype "passive"))
      (node (ref "TP1") (pin "1") (pinfunction "TP_1") (pintype "passive"))
      (node (ref "U1") (pin "48") (pinfunction "VCAP_48") (pintype "power_in"))
    )
    (net (code "88") (name "Net-(TP2-TP)") (class "Default")
      (node (ref "C15") (pin "1") (pinfunction "1_1") (pintype "passive"))
      (node (ref "C16") (pin "1") (pinfunction "1_1") (pintype "passive"))
      (node (ref "TP2") (pin "1") (pinfunction "TP_1") (pintype "passive"))
      (node (ref "U1") (pin "73") (pinfunction "VCAP_73") (pintype "power_in"))
    )
    (net (code "89") (name "Net-(U1B-BOOT0)") (class "Default")
      (node (ref "R2") (pin "1") (pinfunction "1_1") (pintype "passive"))
      (node (ref "R3") (pin "2") (pinfunction "2_2") (pintype "passive"))
      (node (ref "U1") (pin "94") (pinfunction "BOOT0_94") (pintype "input"))
    )
    (net (code "90") (name "Net-(U1B-PA15)") (class "Default")
      (node (ref "R6") (pin "2") (pinfunction "2_2") (pintype "passive"))
      (node (ref "U1") (pin "77") (pinfunction "PA15_77") (pintype "bidirectional"))
    )
    (net (code "91") (name "Net-(U1B-PD4)") (class "Default")
      (node (ref "R4") (pin "1") (pinfunction "1_1") (pintype "passive"))
      (node (ref "U1") (pin "85") (pinfunction "PD4_85") (pintype "bidirectional"))
    )
    (net (code "92") (name "Net-(U1B-~{RST})") (class "Default")
      (node (ref "C1") (pin "1") (pinfunction "1_1") (pintype "passive"))
      (node (ref "R1") (pin "1") (pinfunction "1_1") (pintype "passive"))
      (node (ref "U1") (pin "14") (pinfunction "~{RST}_14") (pintype "input"))
    )
    (net (code "93") (name "Net-(U3-VD)") (class "Default")
      (node (ref "C3") (pin "1") (pinfunction "1_1") (pintype "passive"))
      (node (ref "C4") (pin "1") (pinfunction "1_1") (pintype "passive"))
      (node (ref "R7") (pin "2") (pinfunction "2_2") (pintype "passive"))
      (node (ref "U3") (pin "13") (pinfunction "VD_13") (pintype "power_in"))
    )
    (net (code "94") (name "VCC") (class "Default")
      (node (ref "LS1") (pin "P") (pinfunction "P_P") (pintype "passive"))
    )
    (net (code "95") (name "unconnected-(J4-NC-Pad7)") (class "Default")
      (node (ref "J4") (pin "7") (pinfunction "NC_7") (pintype "input+no_connect"))
    )
    (net (code "96") (name "unconnected-(J4-NC-Pad9)") (class "Default")
      (node (ref "J4") (pin "9") (pinfunction "NC_9") (pintype "input+no_connect"))
    )
    (net (code "97") (name "unconnected-(J4-TDI-Pad8)") (class "Default")
      (node (ref "J4") (pin "8") (pinfunction "TDI_8") (pintype "input+no_connect"))
    )
    (net (code "98") (name "unconnected-(U1B-PA0-Pad22)") (class "Default")
      (node (ref "U1") (pin "22") (pinfunction "PA0_22") (pintype "bidirectional"))
    )
    (net (code "99") (name "unconnected-(U1B-PA1-Pad23)") (class "Default")
      (node (ref "U1") (pin "23") (pinfunction "PA1_23") (pintype "bidirectional"))
    )
    (net (code "100") (name "unconnected-(U1B-PA2-Pad24)") (class "Default")
      (node (ref "U1") (pin "24") (pinfunction "PA2_24") (pintype "bidirectional"))
    )
    (net (code "101") (name "unconnected-(U1B-PA3-Pad25)") (class "Default")
      (node (ref "U1") (pin "25") (pinfunction "PA3_25") (pintype "bidirectional"))
    )
    (net (code "102") (name "unconnected-(U1B-PA8-Pad67)") (class "Default")
      (node (ref "U1") (pin "67") (pinfunction "PA8_67") (pintype "bidirectional"))
    )
    (net (code "103") (name "unconnected-(U1B-PA9-Pad68)") (class "Default")
      (node (ref "U1") (pin "68") (pinfunction "PA9_68") (pintype "bidirectional"))
    )
    (net (code "104") (name "unconnected-(U1B-PA10-Pad69)") (class "Default")
      (node (ref "U1") (pin "69") (pinfunction "PA10_69") (pintype "bidirectional"))
    )
    (net (code "105") (name "unconnected-(U1B-PA11-Pad70)") (class "Default")
      (node (ref "U1") (pin "70") (pinfunction "PA11_70") (pintype "bidirectional"))
    )
    (net (code "106") (name "unconnected-(U1B-PA12-Pad71)") (class "Default")
      (node (ref "U1") (pin "71") (pinfunction "PA12_71") (pintype "bidirectional"))
    )
    (net (code "107") (name "unconnected-(U1B-PB0-Pad34)") (class "Default")
      (node (ref "U1") (pin "34") (pinfunction "PB0_34") (pintype "bidirectional"))
    )
    (net (code "108") (name "unconnected-(U1B-PB1-Pad35)") (class "Default")
      (node (ref "U1") (pin "35") (pinfunction "PB1_35") (pintype "bidirectional"))
    )
    (net (code "109") (name "unconnected-(U1B-PB2-Pad36)") (class "Default")
      (node (ref "U1") (pin "36") (pinfunction "PB2_36") (pintype "bidirectional"))
    )
    (net (code "110") (name "unconnected-(U1B-PB4-Pad90)") (class "Default")
      (node (ref "U1") (pin "90") (pinfunction "PB4_90") (pintype "bidirectional"))
    )
    (net (code "111") (name "unconnected-(U1B-PB5-Pad91)") (class "Default")
      (node (ref "U1") (pin "91") (pinfunction "PB5_91") (pintype "bidirectional"))
    )
    (net (code "112") (name "unconnected-(U1B-PB6-Pad92)") (class "Default")
      (node (ref "U1") (pin "92") (pinfunction "PB6_92") (pintype "bidirectional"))
    )
    (net (code "113") (name "unconnected-(U1B-PB7-Pad93)") (class "Default")
      (node (ref "U1") (pin "93") (pinfunction "PB7_93") (pintype "bidirectional"))
    )
    (net (code "114") (name "unconnected-(U1B-PB8-Pad95)") (class "Default")
      (node (ref "U1") (pin "95") (pinfunction "PB8_95") (pintype "bidirectional"))
    )
    (net (code "115") (name "unconnected-(U1B-PB9-Pad96)") (class "Default")
      (node (ref "U1") (pin "96") (pinfunction "PB9_96") (pintype "bidirectional"))
    )
    (net (code "116") (name "unconnected-(U1B-PB10-Pad46)") (class "Default")
      (node (ref "U1") (pin "46") (pinfunction "PB10_46") (pintype "bidirectional"))
    )
    (net (code "117") (name "unconnected-(U1B-PB11-Pad47)") (class "Default")
      (node (ref "U1") (pin "47") (pinfunction "PB11_47") (pintype "bidirectional"))
    )
    (net (code "118") (name "unconnected-(U1B-PC0-Pad15)") (class "Default")
      (node (ref "U1") (pin "15") (pinfunction "PC0_15") (pintype "bidirectional"))
    )
    (net (code "119") (name "unconnected-(U1B-PC1-Pad16)") (class "Default")
      (node (ref "U1") (pin "16") (pinfunction "PC1_16") (pintype "bidirectional"))
    )
    (net (code "120") (name "unconnected-(U1B-PC2_C-Pad17)") (class "Default")
      (node (ref "U1") (pin "17") (pinfunction "PC2_C_17") (pintype "bidirectional"))
    )
    (net (code "121") (name "unconnected-(U1B-PC3_C-Pad18)") (class "Default")
      (node (ref "U1") (pin "18") (pinfunction "PC3_C_18") (pintype "bidirectional"))
    )
    (net (code "122") (name "unconnected-(U1B-PC4-Pad32)") (class "Default")
      (node (ref "U1") (pin "32") (pinfunction "PC4_32") (pintype "bidirectional"))
    )
    (net (code "123") (name "unconnected-(U1B-PC5-Pad33)") (class "Default")
      (node (ref "U1") (pin "33") (pinfunction "PC5_33") (pintype "bidirectional"))
    )
    (net (code "124") (name "unconnected-(U1B-PC6-Pad63)") (class "Default")
      (node (ref "U1") (pin "63") (pinfunction "PC6_63") (pintype "bidirectional"))
    )
    (net (code "125") (name "unconnected-(U1B-PC7-Pad64)") (class "Default")
      (node (ref "U1") (pin "64") (pinfunction "PC7_64") (pintype "bidirectional"))
    )
    (net (code "126") (name "unconnected-(U1B-PC8-Pad65)") (class "Default")
      (node (ref "U1") (pin "65") (pinfunction "PC8_65") (pintype "bidirectional"))
    )
    (net (code "127") (name "unconnected-(U1B-PC9-Pad66)") (class "Default")
      (node (ref "U1") (pin "66") (pinfunction "PC9_66") (pintype "bidirectional"))
    )
    (net (code "128") (name "unconnected-(U1B-PC13-Pad7)") (class "Default")
      (node (ref "U1") (pin "7") (pinfunction "PC13_7") (pintype "bidirectional"))
    )
    (net (code "129") (name "unconnected-(U1B-PD2-Pad83)") (class "Default")
      (node (ref "U1") (pin "83") (pinfunction "PD2_83") (pintype "bidirectional"))
    )
    (net (code "130") (name "unconnected-(U1B-PD3-Pad84)") (class "Default")
      (node (ref "U1") (pin "84") (pinfunction "PD3_84") (pintype "bidirectional"))
    )
    (net (code "131") (name "unconnected-(U1B-PD5-Pad86)") (class "Default")
      (node (ref "U1") (pin "86") (pinfunction "PD5_86") (pintype "bidirectional"))
    )
    (net (code "132") (name "unconnected-(U1B-PD6-Pad87)") (class "Default")
      (node (ref "U1") (pin "87") (pinfunction "PD6_87") (pintype "bidirectional"))
    )
    (net (code "133") (name "unconnected-(U1B-PD7-Pad88)") (class "Default")
      (node (ref "U1") (pin "88") (pinfunction "PD7_88") (pintype "bidirectional"))
    )
    (net (code "134") (name "unconnected-(U1B-PD8-Pad55)") (class "Default")
      (node (ref "U1") (pin "55") (pinfunction "PD8_55") (pintype "bidirectional"))
    )
    (net (code "135") (name "unconnected-(U1B-PD9-Pad56)") (class "Default")
      (node (ref "U1") (pin "56") (pinfunction "PD9_56") (pintype "bidirectional"))
    )
    (net (code "136") (name "unconnected-(U1B-PD10-Pad57)") (class "Default")
      (node (ref "U1") (pin "57") (pinfunction "PD10_57") (pintype "bidirectional"))
    )
    (net (code "137") (name "unconnected-(U1B-PD11-Pad58)") (class "Default")
      (node (ref "U1") (pin "58") (pinfunction "PD11_58") (pintype "bidirectional"))
    )
    (net (code "138") (name "unconnected-(U1B-PD12-Pad59)") (class "Default")
      (node (ref "U1") (pin "59") (pinfunction "PD12_59") (pintype "bidirectional"))
    )
    (net (code "139") (name "unconnected-(U1B-PD13-Pad60)") (class "Default")
      (node (ref "U1") (pin "60") (pinfunction "PD13_60") (pintype "bidirectional"))
    )
    (net (code "140") (name "unconnected-(U1B-PD14-Pad61)") (class "Default")
      (node (ref "U1") (pin "61") (pinfunction "PD14_61") (pintype "bidirectional"))
    )
    (net (code "141") (name "unconnected-(U1B-PD15-Pad62)") (class "Default")
      (node (ref "U1") (pin "62") (pinfunction "PD15_62") (pintype "bidirectional"))
    )
    (net (code "142") (name "unconnected-(U1B-PE0-Pad97)") (class "Default")
      (node (ref "U1") (pin "97") (pinfunction "PE0_97") (pintype "bidirectional"))
    )
    (net (code "143") (name "unconnected-(U1B-PE1-Pad98)") (class "Default")
      (node (ref "U1") (pin "98") (pinfunction "PE1_98") (pintype "bidirectional"))
    )
    (net (code "144") (name "unconnected-(U1B-PE2-Pad1)") (class "Default")
      (node (ref "U1") (pin "1") (pinfunction "PE2_1") (pintype "bidirectional"))
    )
    (net (code "145") (name "unconnected-(U1B-PE3-Pad2)") (class "Default")
      (node (ref "U1") (pin "2") (pinfunction "PE3_2") (pintype "bidirectional"))
    )
    (net (code "146") (name "unconnected-(U1B-PE4-Pad3)") (class "Default")
      (node (ref "U1") (pin "3") (pinfunction "PE4_3") (pintype "bidirectional"))
    )
    (net (code "147") (name "unconnected-(U1B-PE5-Pad4)") (class "Default")
      (node (ref "U1") (pin "4") (pinfunction "PE5_4") (pintype "bidirectional"))
    )
    (net (code "148") (name "unconnected-(U1B-PE6-Pad5)") (class "Default")
      (node (ref "U1") (pin "5") (pinfunction "PE6_5") (pintype "bidirectional"))
    )
    (net (code "149") (name "unconnected-(U1B-PE7-Pad37)") (class "Default")
      (node (ref "U1") (pin "37") (pinfunction "PE7_37") (pintype "bidirectional"))
    )
    (net (code "150") (name "unconnected-(U1B-PE8-Pad38)") (class "Default")
      (node (ref "U1") (pin "38") (pinfunction "PE8_38") (pintype "bidirectional"))
    )
    (net (code "151") (name "unconnected-(U1B-PE9-Pad39)") (class "Default")
      (node (ref "U1") (pin "39") (pinfunction "PE9_39") (pintype "bidirectional"))
    )
    (net (code "152") (name "unconnected-(U1B-PE10-Pad40)") (class "Default")
      (node (ref "U1") (pin "40") (pinfunction "PE10_40") (pintype "bidirectional"))
    )
    (net (code "153") (name "unconnected-(U1B-PE15-Pad45)") (class "Default")
      (node (ref "U1") (pin "45") (pinfunction "PE15_45") (pintype "bidirectional"))
    )
  )
)
